# SN74HC165_Shift-In_Breakout-v11.net
KiCad netlist of a schematic drawn in EAGLE
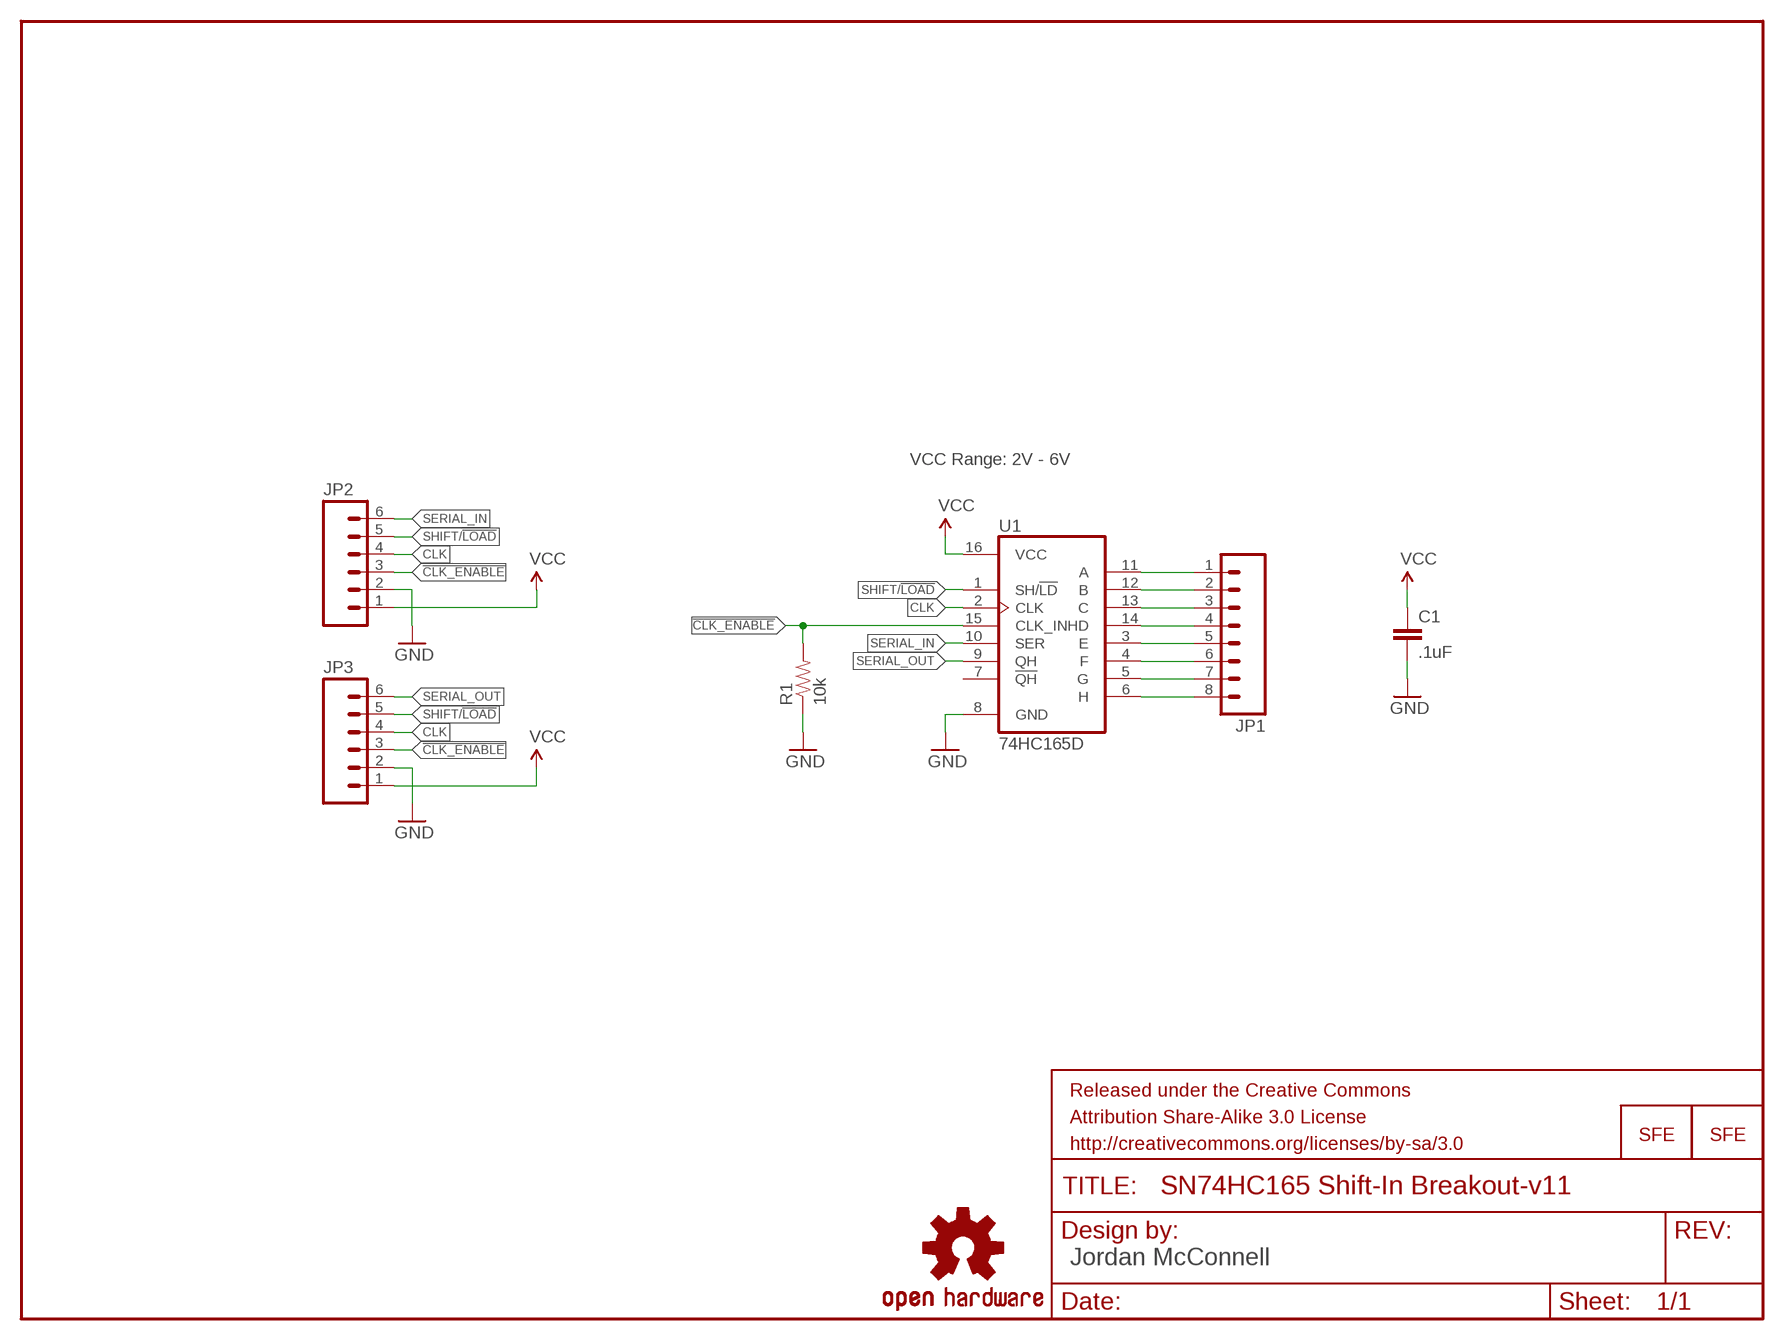
[diagram p0: schematic, sheet 1]

(export (version "E")
  (design (tool "Eeschema 10.0.6"))
  (components
    (comp (ref "C1")
      (value ".1uF")
      (footprint "eagle-import:0402-CAP")
      (libsource (lib "eagle-import") (part "CAP0402-CAP"))
    )
    (comp (ref "FRAME1")
      (value "FRAME-LETTER")
      (footprint "eagle-import:CREATIVE_COMMONS")
      (libsource (lib "eagle-import") (part "FRAME-LETTER"))
    )
    (comp (ref "JP1")
      (value "M081X08")
      (footprint "eagle-import:1X08")
      (libsource (lib "eagle-import") (part "M081X08"))
    )
    (comp (ref "JP2")
      (value "M06SIP")
      (footprint "eagle-import:1X06")
      (libsource (lib "eagle-import") (part "M06SIP"))
    )
    (comp (ref "JP3")
      (value "M06SIP")
      (footprint "eagle-import:1X06")
      (libsource (lib "eagle-import") (part "M06SIP"))
    )
    (comp (ref "JP4")
      (value "LOGO-SFESK")
      (footprint "eagle-import:SFE-LOGO-FLAME")
      (libsource (lib "eagle-import") (part "LOGO-SFESK"))
    )
    (comp (ref "JP5")
      (value "LOGO-SFENEW")
      (footprint "eagle-import:SFE-NEW-WEBLOGO")
      (libsource (lib "eagle-import") (part "LOGO-SFENEW"))
    )
    (comp (ref "R1")
      (value "10k")
      (footprint "eagle-import:0402-RES")
      (libsource (lib "eagle-import") (part "RESISTOR0402-RES"))
    )
    (comp (ref "U$1")
      (value "OSHW-LOGOS")
      (footprint "eagle-import:OSHW-LOGO-S")
      (libsource (lib "eagle-import") (part "OSHW-LOGOS"))
    )
    (comp (ref "U1")
      (value "74HC165D")
      (footprint "eagle-import:SO16")
      (libsource (lib "eagle-import") (part "74165D"))
    )
  )
  (nets
    (net (code "1") (name "/SHIFT{slash}~{LOAD}") (class "Default")
      (node (ref "JP2") (pin "5") (pinfunction "5_5") (pintype "passive"))
      (node (ref "JP3") (pin "5") (pinfunction "5_5") (pintype "passive"))
      (node (ref "U1") (pin "1") (pinfunction "SH/~{LD}_1") (pintype "input"))
    )
    (net (code "2") (name "/~{CLK_ENABLE}") (class "Default")
      (node (ref "JP2") (pin "3") (pinfunction "3_3") (pintype "passive"))
      (node (ref "JP3") (pin "3") (pinfunction "3_3") (pintype "passive"))
      (node (ref "R1") (pin "2") (pinfunction "2_2") (pintype "passive"))
      (node (ref "U1") (pin "15") (pinfunction "CLK_INH_15") (pintype "input"))
    )
    (net (code "3") (name "CLK") (class "Default")
      (node (ref "JP2") (pin "4") (pinfunction "4_4") (pintype "passive"))
      (node (ref "JP3") (pin "4") (pinfunction "4_4") (pintype "passive"))
      (node (ref "U1") (pin "2") (pinfunction "CLK_2") (pintype "input"))
    )
    (net (code "4") (name "GND") (class "Default")
      (node (ref "C1") (pin "2") (pinfunction "2_2") (pintype "passive"))
      (node (ref "JP2") (pin "2") (pinfunction "2_2") (pintype "passive"))
      (node (ref "JP3") (pin "2") (pinfunction "2_2") (pintype "passive"))
      (node (ref "R1") (pin "1") (pinfunction "1_1") (pintype "passive"))
      (node (ref "U1") (pin "8") (pinfunction "GND_8") (pintype "power_in"))
    )
    (net (code "5") (name "Net-(U1-A)") (class "Default")
      (node (ref "JP1") (pin "1") (pinfunction "1_1") (pintype "passive"))
      (node (ref "U1") (pin "11") (pinfunction "A_11") (pintype "tri_state"))
    )
    (net (code "6") (name "Net-(U1-B)") (class "Default")
      (node (ref "JP1") (pin "2") (pinfunction "2_2") (pintype "passive"))
      (node (ref "U1") (pin "12") (pinfunction "B_12") (pintype "tri_state"))
    )
    (net (code "7") (name "Net-(U1-C)") (class "Default")
      (node (ref "JP1") (pin "3") (pinfunction "3_3") (pintype "passive"))
      (node (ref "U1") (pin "13") (pinfunction "C_13") (pintype "tri_state"))
    )
    (net (code "8") (name "Net-(U1-D)") (class "Default")
      (node (ref "JP1") (pin "4") (pinfunction "4_4") (pintype "passive"))
      (node (ref "U1") (pin "14") (pinfunction "D_14") (pintype "tri_state"))
    )
    (net (code "9") (name "Net-(U1-E)") (class "Default")
      (node (ref "JP1") (pin "5") (pinfunction "5_5") (pintype "passive"))
      (node (ref "U1") (pin "3") (pinfunction "E_3") (pintype "tri_state"))
    )
    (net (code "10") (name "Net-(U1-F)") (class "Default")
      (node (ref "JP1") (pin "6") (pinfunction "6_6") (pintype "passive"))
      (node (ref "U1") (pin "4") (pinfunction "F_4") (pintype "tri_state"))
    )
    (net (code "11") (name "Net-(U1-G)") (class "Default")
      (node (ref "JP1") (pin "7") (pinfunction "7_7") (pintype "passive"))
      (node (ref "U1") (pin "5") (pinfunction "G_5") (pintype "tri_state"))
    )
    (net (code "12") (name "Net-(U1-H)") (class "Default")
      (node (ref "JP1") (pin "8") (pinfunction "8_8") (pintype "passive"))
      (node (ref "U1") (pin "6") (pinfunction "H_6") (pintype "tri_state"))
    )
    (net (code "13") (name "SERIAL_IN") (class "Default")
      (node (ref "JP2") (pin "6") (pinfunction "6_6") (pintype "passive"))
      (node (ref "U1") (pin "10") (pinfunction "SER_10") (pintype "input"))
    )
    (net (code "14") (name "SERIAL_OUT") (class "Default")
      (node (ref "JP3") (pin "6") (pinfunction "6_6") (pintype "passive"))
      (node (ref "U1") (pin "9") (pinfunction "QH_9") (pintype "tri_state"))
    )
    (net (code "15") (name "VCC") (class "Default")
      (node (ref "C1") (pin "1") (pinfunction "1_1") (pintype "passive"))
      (node (ref "JP2") (pin "1") (pinfunction "1_1") (pintype "passive"))
      (node (ref "JP3") (pin "1") (pinfunction "1_1") (pintype "passive"))
      (node (ref "U1") (pin "16") (pinfunction "VCC_16") (pintype "power_in"))
    )
    (net (code "16") (name "unconnected-(U1-~{QH}-Pad7)") (class "Default")
      (node (ref "U1") (pin "7") (pinfunction "~{QH}_7") (pintype "input"))
    )
  )
)
